# uln2003_Shematics.net
KiCad netlist of a schematic drawn in Altium Designer
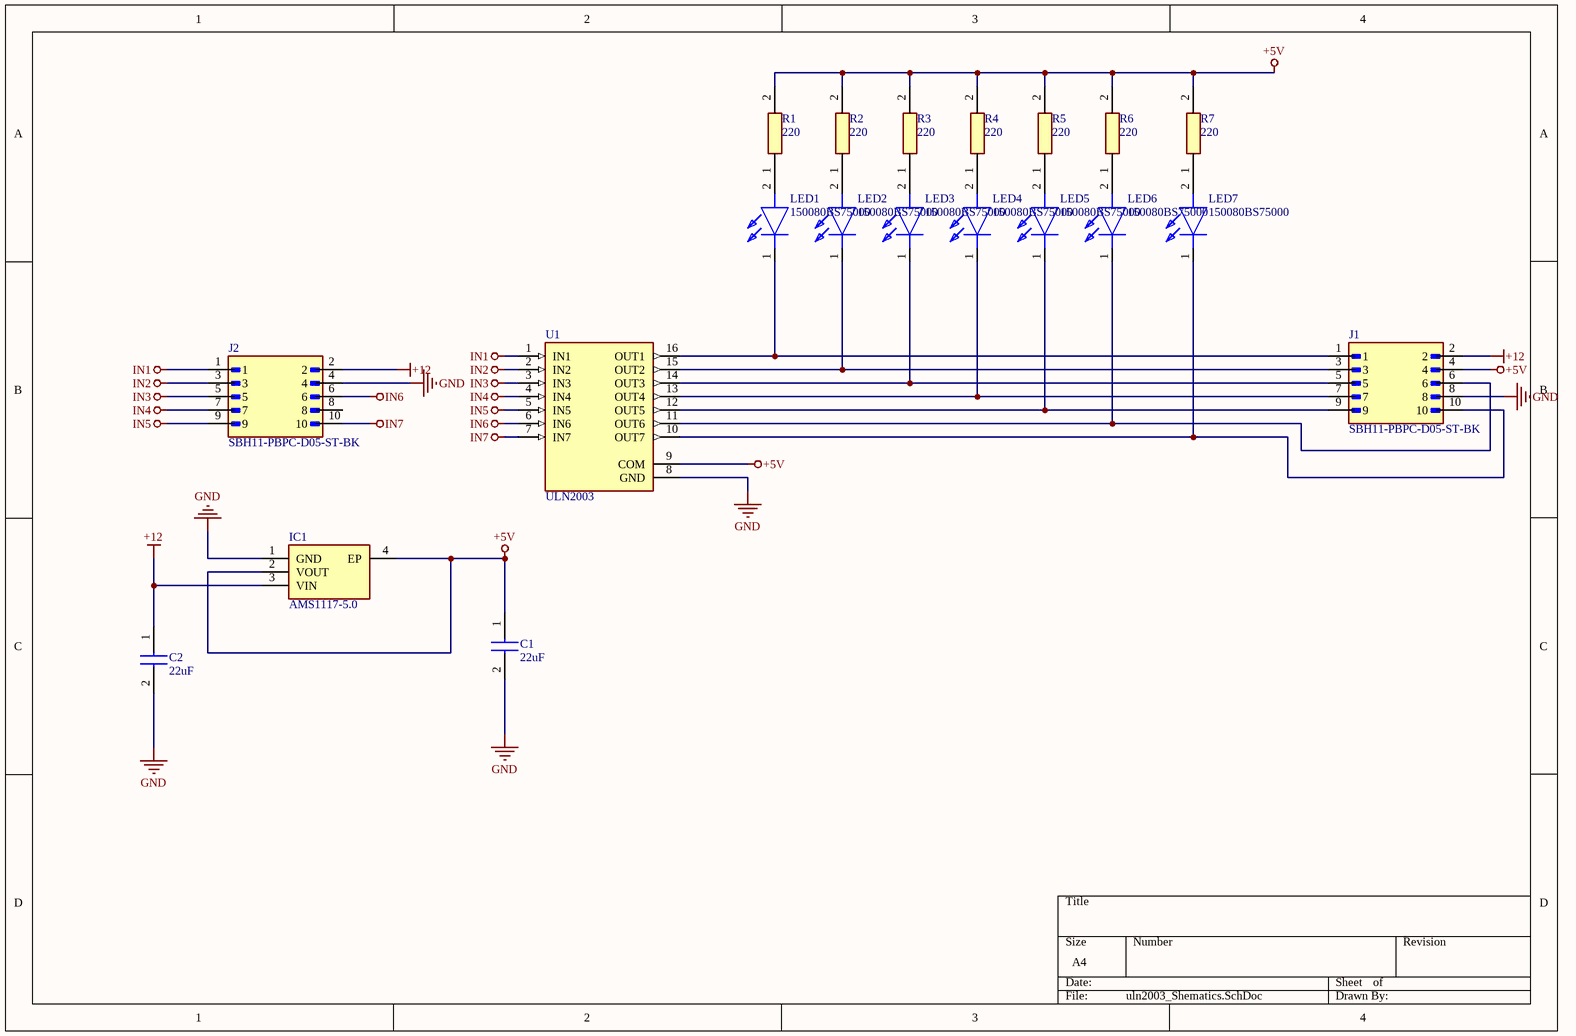
[diagram p0: uln2003_Shematics.SchDoc]

(export (version "E")
  (design (tool "Eeschema 10.0.6"))
  (components
    (comp (ref "C1")
      (value "22uF")
      (footprint "SamacSys:CAPC2013X140N")
      (description "Capacitor")
      (fields
        (field (name "MANUFACTURER_PART_NUMBER") "08053C474JAT2A")
        (field (name "MOUSER PART NUMBER") "581-08053C474JAT2A")
      )
      (libsource (lib "SamacSys") (part "08053C474JAT2A"))
    )
    (comp (ref "C2")
      (value "22uF")
      (footprint "SamacSys:CAPC2013X140N")
      (description "Capacitor")
      (fields
        (field (name "MANUFACTURER_PART_NUMBER") "08053C474JAT2A")
        (field (name "MOUSER PART NUMBER") "581-08053C474JAT2A")
      )
      (libsource (lib "SamacSys") (part "08053C474JAT2A"))
    )
    (comp (ref "IC1")
      (value "AMS1117-5.0")
      (footprint "SOT229P700X180-4N")
      (description "Integrated Circuit")
      (libsource (lib "*") (part "AMS1117-5.0"))
    )
    (comp (ref "J1")
      (value "SBH11-PBPC-D05-ST-BK")
      (footprint "SULLINS_SBH11-PBPC-D05-ST-BK")
      (description "10 Position Total Dual Row 2.54 mm Pitch Straight Male Shrouded Box Header")
      (fields (field (name "MF") "Sullins Connector"))
      (libsource (lib "SBH11-PBPC-D05-ST-BK") (part "SBH11-PBPC-D05-ST-BK"))
    )
    (comp (ref "J2")
      (value "SBH11-PBPC-D05-ST-BK")
      (footprint "SULLINS_SBH11-PBPC-D05-ST-BK")
      (description "10 Position Total Dual Row 2.54 mm Pitch Straight Male Shrouded Box Header")
      (fields (field (name "MF") "Sullins Connector"))
      (libsource (lib "SBH11-PBPC-D05-ST-BK") (part "SBH11-PBPC-D05-ST-BK"))
    )
    (comp (ref "LED1")
      (value "150080BS75000")
      (footprint "SamacSys:LEDC2012X80N")
      (description "LED")
      (fields (field (name "MOUSER PART NUMBER") "710-150080BS75000"))
      (libsource (lib "SamacSys") (part "150080BS75000"))
    )
    (comp (ref "LED2")
      (value "150080BS75000")
      (footprint "SamacSys:LEDC2012X80N")
      (description "LED")
      (fields (field (name "MOUSER PART NUMBER") "710-150080BS75000"))
      (libsource (lib "SamacSys") (part "150080BS75000"))
    )
    (comp (ref "LED3")
      (value "150080BS75000")
      (footprint "SamacSys:LEDC2012X80N")
      (description "LED")
      (fields (field (name "MOUSER PART NUMBER") "710-150080BS75000"))
      (libsource (lib "SamacSys") (part "150080BS75000"))
    )
    (comp (ref "LED4")
      (value "150080BS75000")
      (footprint "SamacSys:LEDC2012X80N")
      (description "LED")
      (fields (field (name "MOUSER PART NUMBER") "710-150080BS75000"))
      (libsource (lib "SamacSys") (part "150080BS75000"))
    )
    (comp (ref "LED5")
      (value "150080BS75000")
      (footprint "SamacSys:LEDC2012X80N")
      (description "LED")
      (fields (field (name "MOUSER PART NUMBER") "710-150080BS75000"))
      (libsource (lib "SamacSys") (part "150080BS75000"))
    )
    (comp (ref "LED6")
      (value "150080BS75000")
      (footprint "SamacSys:LEDC2012X80N")
      (description "LED")
      (fields (field (name "MOUSER PART NUMBER") "710-150080BS75000"))
      (libsource (lib "SamacSys") (part "150080BS75000"))
    )
    (comp (ref "LED7")
      (value "150080BS75000")
      (footprint "SamacSys:LEDC2012X80N")
      (description "LED")
      (fields (field (name "MOUSER PART NUMBER") "710-150080BS75000"))
      (libsource (lib "SamacSys") (part "150080BS75000"))
    )
    (comp (ref "R1")
      (value "220")
      (footprint "SamacSys:RESC2012X65N")
      (description "Resistor")
      (fields (field (name "MANUFACTURER_PART_NUMBER") "CPF0805B102RE1"))
      (libsource (lib "SamacSys") (part "CPF0805B102RE1"))
    )
    (comp (ref "R2")
      (value "220")
      (footprint "SamacSys:RESC2012X65N")
      (description "Resistor")
      (fields (field (name "MANUFACTURER_PART_NUMBER") "CPF0805B102RE1"))
      (libsource (lib "SamacSys") (part "CPF0805B102RE1"))
    )
    (comp (ref "R3")
      (value "220")
      (footprint "SamacSys:RESC2012X65N")
      (description "Resistor")
      (fields (field (name "MANUFACTURER_PART_NUMBER") "CPF0805B102RE1"))
      (libsource (lib "SamacSys") (part "CPF0805B102RE1"))
    )
    (comp (ref "R4")
      (value "220")
      (footprint "SamacSys:RESC2012X65N")
      (description "Resistor")
      (fields (field (name "MANUFACTURER_PART_NUMBER") "CPF0805B102RE1"))
      (libsource (lib "SamacSys") (part "CPF0805B102RE1"))
    )
    (comp (ref "R5")
      (value "220")
      (footprint "SamacSys:RESC2012X65N")
      (description "Resistor")
      (fields (field (name "MANUFACTURER_PART_NUMBER") "CPF0805B102RE1"))
      (libsource (lib "SamacSys") (part "CPF0805B102RE1"))
    )
    (comp (ref "R6")
      (value "220")
      (footprint "SamacSys:RESC2012X65N")
      (description "Resistor")
      (fields (field (name "MANUFACTURER_PART_NUMBER") "CPF0805B102RE1"))
      (libsource (lib "SamacSys") (part "CPF0805B102RE1"))
    )
    (comp (ref "R7")
      (value "220")
      (footprint "SamacSys:RESC2012X65N")
      (description "Resistor")
      (fields (field (name "MANUFACTURER_PART_NUMBER") "CPF0805B102RE1"))
      (libsource (lib "SamacSys") (part "CPF0805B102RE1"))
    )
    (comp (ref "U1")
      (value "ULN2003")
      (footprint "SOIC127P600X175-16N")
      (description "Bipolar (BJT) Transistor Array 7 NPN Darlington 50V 500mA - - Surface Mount 16-SOIC")
      (fields (field (name "MF") "Texas Instruments"))
      (libsource (lib "ULN2003") (part "ULN2003"))
    )
  )
  (nets
    (net (code "1") (name "+5V") (class "Default")
      (node (ref "C1") (pin "1") (pinfunction "C1_1") (pintype "passive"))
      (node (ref "IC1") (pin "2") (pinfunction "VOUT_2") (pintype "passive"))
      (node (ref "IC1") (pin "4") (pinfunction "EP_4") (pintype "passive"))
      (node (ref "J1") (pin "4") (pinfunction "4_4") (pintype "passive"))
      (node (ref "R1") (pin "2") (pinfunction "2_2") (pintype "passive"))
      (node (ref "R2") (pin "2") (pinfunction "2_2") (pintype "passive"))
      (node (ref "R3") (pin "2") (pinfunction "2_2") (pintype "passive"))
      (node (ref "R4") (pin "2") (pinfunction "2_2") (pintype "passive"))
      (node (ref "R5") (pin "2") (pinfunction "2_2") (pintype "passive"))
      (node (ref "R6") (pin "2") (pinfunction "2_2") (pintype "passive"))
      (node (ref "R7") (pin "2") (pinfunction "2_2") (pintype "passive"))
      (node (ref "U1") (pin "9") (pinfunction "COM_9") (pintype "power_in"))
    )
    (net (code "2") (name "+12") (class "Default")
      (node (ref "C2") (pin "1") (pinfunction "C1_1") (pintype "passive"))
      (node (ref "IC1") (pin "3") (pinfunction "VIN_3") (pintype "passive"))
      (node (ref "J1") (pin "2") (pinfunction "2_2") (pintype "passive"))
      (node (ref "J2") (pin "2") (pinfunction "2_2") (pintype "passive"))
    )
    (net (code "3") (name "GND") (class "Default")
      (node (ref "C1") (pin "2") (pinfunction "C2_2") (pintype "passive"))
      (node (ref "C2") (pin "2") (pinfunction "C2_2") (pintype "passive"))
      (node (ref "IC1") (pin "1") (pinfunction "GND_1") (pintype "passive"))
      (node (ref "J1") (pin "8") (pinfunction "8_8") (pintype "passive"))
      (node (ref "J2") (pin "4") (pinfunction "4_4") (pintype "passive"))
      (node (ref "U1") (pin "8") (pinfunction "GND_8") (pintype "power_in"))
    )
    (net (code "4") (name "IN1") (class "Default")
      (node (ref "J2") (pin "1") (pinfunction "1_1") (pintype "passive"))
      (node (ref "U1") (pin "1") (pinfunction "IN1_1") (pintype "input"))
    )
    (net (code "5") (name "IN2") (class "Default")
      (node (ref "J2") (pin "3") (pinfunction "3_3") (pintype "passive"))
      (node (ref "U1") (pin "2") (pinfunction "IN2_2") (pintype "input"))
    )
    (net (code "6") (name "IN3") (class "Default")
      (node (ref "J2") (pin "5") (pinfunction "5_5") (pintype "passive"))
      (node (ref "U1") (pin "3") (pinfunction "IN3_3") (pintype "input"))
    )
    (net (code "7") (name "IN4") (class "Default")
      (node (ref "J2") (pin "7") (pinfunction "7_7") (pintype "passive"))
      (node (ref "U1") (pin "4") (pinfunction "IN4_4") (pintype "input"))
    )
    (net (code "8") (name "IN5") (class "Default")
      (node (ref "J2") (pin "9") (pinfunction "9_9") (pintype "passive"))
      (node (ref "U1") (pin "5") (pinfunction "IN5_5") (pintype "input"))
    )
    (net (code "9") (name "IN6") (class "Default")
      (node (ref "J2") (pin "6") (pinfunction "6_6") (pintype "passive"))
      (node (ref "U1") (pin "6") (pinfunction "IN6_6") (pintype "input"))
    )
    (net (code "10") (name "IN7") (class "Default")
      (node (ref "J2") (pin "10") (pinfunction "10_10") (pintype "passive"))
      (node (ref "U1") (pin "7") (pinfunction "IN7_7") (pintype "input"))
    )
    (net (code "11") (name "Net-(LED1-A)") (class "Default")
      (node (ref "LED1") (pin "2") (pinfunction "A_2") (pintype "passive"))
      (node (ref "R1") (pin "1") (pinfunction "1_1") (pintype "passive"))
    )
    (net (code "12") (name "Net-(LED1-K)") (class "Default")
      (node (ref "J1") (pin "1") (pinfunction "1_1") (pintype "passive"))
      (node (ref "LED1") (pin "1") (pinfunction "K_1") (pintype "passive"))
      (node (ref "U1") (pin "16") (pinfunction "OUT1_16") (pintype "output"))
    )
    (net (code "13") (name "Net-(LED2-A)") (class "Default")
      (node (ref "LED2") (pin "2") (pinfunction "A_2") (pintype "passive"))
      (node (ref "R2") (pin "1") (pinfunction "1_1") (pintype "passive"))
    )
    (net (code "14") (name "Net-(LED2-K)") (class "Default")
      (node (ref "J1") (pin "3") (pinfunction "3_3") (pintype "passive"))
      (node (ref "LED2") (pin "1") (pinfunction "K_1") (pintype "passive"))
      (node (ref "U1") (pin "15") (pinfunction "OUT2_15") (pintype "output"))
    )
    (net (code "15") (name "Net-(LED3-A)") (class "Default")
      (node (ref "LED3") (pin "2") (pinfunction "A_2") (pintype "passive"))
      (node (ref "R3") (pin "1") (pinfunction "1_1") (pintype "passive"))
    )
    (net (code "16") (name "Net-(LED3-K)") (class "Default")
      (node (ref "J1") (pin "5") (pinfunction "5_5") (pintype "passive"))
      (node (ref "LED3") (pin "1") (pinfunction "K_1") (pintype "passive"))
      (node (ref "U1") (pin "14") (pinfunction "OUT3_14") (pintype "output"))
    )
    (net (code "17") (name "Net-(LED4-A)") (class "Default")
      (node (ref "LED4") (pin "2") (pinfunction "A_2") (pintype "passive"))
      (node (ref "R4") (pin "1") (pinfunction "1_1") (pintype "passive"))
    )
    (net (code "18") (name "Net-(LED4-K)") (class "Default")
      (node (ref "J1") (pin "7") (pinfunction "7_7") (pintype "passive"))
      (node (ref "LED4") (pin "1") (pinfunction "K_1") (pintype "passive"))
      (node (ref "U1") (pin "13") (pinfunction "OUT4_13") (pintype "output"))
    )
    (net (code "19") (name "Net-(LED5-A)") (class "Default")
      (node (ref "LED5") (pin "2") (pinfunction "A_2") (pintype "passive"))
      (node (ref "R5") (pin "1") (pinfunction "1_1") (pintype "passive"))
    )
    (net (code "20") (name "Net-(LED5-K)") (class "Default")
      (node (ref "J1") (pin "9") (pinfunction "9_9") (pintype "passive"))
      (node (ref "LED5") (pin "1") (pinfunction "K_1") (pintype "passive"))
      (node (ref "U1") (pin "12") (pinfunction "OUT5_12") (pintype "output"))
    )
    (net (code "21") (name "Net-(LED6-A)") (class "Default")
      (node (ref "LED6") (pin "2") (pinfunction "A_2") (pintype "passive"))
      (node (ref "R6") (pin "1") (pinfunction "1_1") (pintype "passive"))
    )
    (net (code "22") (name "Net-(LED6-K)") (class "Default")
      (node (ref "J1") (pin "6") (pinfunction "6_6") (pintype "passive"))
      (node (ref "LED6") (pin "1") (pinfunction "K_1") (pintype "passive"))
      (node (ref "U1") (pin "11") (pinfunction "OUT6_11") (pintype "output"))
    )
    (net (code "23") (name "Net-(LED7-A)") (class "Default")
      (node (ref "LED7") (pin "2") (pinfunction "A_2") (pintype "passive"))
      (node (ref "R7") (pin "1") (pinfunction "1_1") (pintype "passive"))
    )
    (net (code "24") (name "Net-(LED7-K)") (class "Default")
      (node (ref "J1") (pin "10") (pinfunction "10_10") (pintype "passive"))
      (node (ref "LED7") (pin "1") (pinfunction "K_1") (pintype "passive"))
      (node (ref "U1") (pin "10") (pinfunction "OUT7_10") (pintype "output"))
    )
    (net (code "25") (name "unconnected-(J2-Pad8)") (class "Default")
      (node (ref "J2") (pin "8") (pinfunction "8_8") (pintype "passive"))
    )
  )
)
